# machnguon.net
KiCad netlist of a schematic drawn in Altium Designer
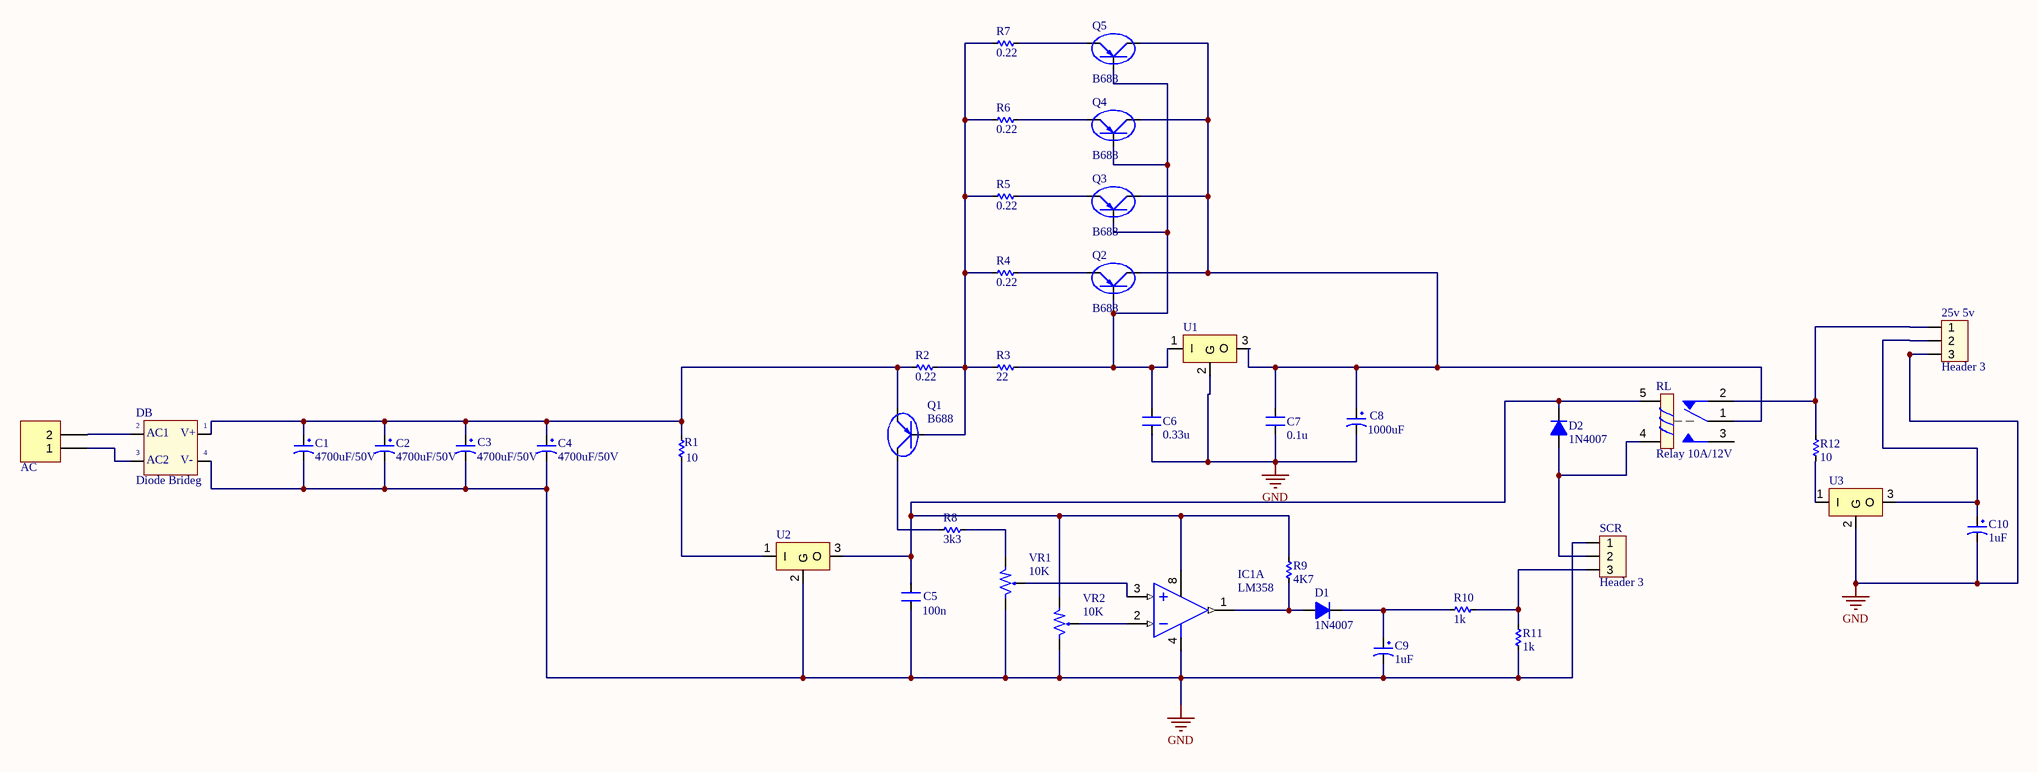
[diagram p0: machnguon.SchDoc]

(export (version "E")
  (design (tool "Eeschema 10.0.6"))
  (components
    (comp (ref "25v 5v")
      (value "Header 3")
      (footprint "HED3")
      (description "Header 3 (Green)")
      (libsource (lib "syhaunguyen__1") (part "Hed3"))
    )
    (comp (ref "AC")
      (value "Header 2_1")
      (footprint "HED2")
      (description "Header, 2-Pin")
      (fields (field (name "MANUFACTURER") "Generic Components"))
      (libsource (lib "syhaunguyen__1") (part "Header 2_1"))
    )
    (comp (ref "C1")
      (value "4700uF/50V")
      (footprint "CP4/8.5")
      (description "Cap 4700uF/50V")
      (libsource (lib "syhaunguyen__1") (part "CP7"))
    )
    (comp (ref "C2")
      (value "4700uF/50V")
      (footprint "CP4/8.5")
      (description "Cap 4700uF/50V")
      (libsource (lib "syhaunguyen__1") (part "CP7"))
    )
    (comp (ref "C3")
      (value "4700uF/50V")
      (footprint "CP4/8.5")
      (description "Cap 4700uF/50V")
      (libsource (lib "syhaunguyen__1") (part "CP7"))
    )
    (comp (ref "C4")
      (value "4700uF/50V")
      (footprint "CP4/8.5")
      (description "Cap 4700uF/50V")
      (libsource (lib "syhaunguyen__1") (part "CP7"))
    )
    (comp (ref "C5")
      (value "100n")
      (footprint "CN1")
      (description "Cap np  1pF - 472pF")
      (libsource (lib "syhaunguyen__1") (part "CN1"))
    )
    (comp (ref "C6")
      (value "0.33u")
      (footprint "CN1")
      (description "Cap np  1pF - 472pF")
      (libsource (lib "syhaunguyen__1") (part "CN1"))
    )
    (comp (ref "C7")
      (value "0.1u")
      (footprint "CN1")
      (description "Cap np  1pF - 472pF")
      (libsource (lib "syhaunguyen__1") (part "CN1"))
    )
    (comp (ref "C8")
      (value "1000uF")
      (footprint "CP1.5/3.4")
      (description "Cap 1000uF/16V - 220uF/50V")
      (libsource (lib "syhaunguyen__1") (part "CP4"))
    )
    (comp (ref "C9")
      (value "1uF")
      (footprint "CP1/2")
      (description "Cap P  0,1uF < 22uF , 16 - 50V")
      (libsource (lib "syhaunguyen__1") (part "CP1"))
    )
    (comp (ref "C10")
      (value "1uF")
      (footprint "CP1/2")
      (description "Cap P  0,1uF < 22uF , 16 - 50V")
      (libsource (lib "syhaunguyen__1") (part "CP1"))
    )
    (comp (ref "D1")
      (value "1N4007")
      (footprint "D1A")
      (description "Diode 1A")
      (libsource (lib "syhaunguyen__1") (part "D1A"))
    )
    (comp (ref "D2")
      (value "1N4007")
      (footprint "D1A")
      (description "Diode 1A")
      (libsource (lib "syhaunguyen__1") (part "D1A"))
    )
    (comp (ref "DB")
      (value "Diode Brideg")
      (footprint "CAU 5A")
      (description "Convert AC to DC voltage, 4 pin")
      (libsource (lib "syhaunguyen__1") (part "DB"))
    )
    (comp (ref "IC1")
      (value "LM358")
      (footprint "DIP8")
      (description "Low-Power Dual Operational Amplifier")
      (libsource (lib "Library1") (part "LM358"))
    )
    (comp (ref "Q1")
      (value "B688")
      (footprint "QTO-247")
      (description "Transistor Power Supply")
      (libsource (lib "") (part "B688_1"))
    )
    (comp (ref "Q2")
      (value "B688")
      (footprint "QTO-247")
      (description "Transistor Power Supply")
      (libsource (lib "syhaunguyen__1") (part "B688"))
    )
    (comp (ref "Q3")
      (value "B688")
      (footprint "QTO-247")
      (description "Transistor Power Supply")
      (libsource (lib "syhaunguyen__1") (part "B688"))
    )
    (comp (ref "Q4")
      (value "B688")
      (footprint "QTO-247")
      (description "Transistor Power Supply")
      (libsource (lib "syhaunguyen__1") (part "B688"))
    )
    (comp (ref "Q5")
      (value "B688")
      (footprint "QTO-247")
      (description "Transistor Power Supply")
      (libsource (lib "syhaunguyen__1") (part "B688"))
    )
    (comp (ref "R1")
      (value "10")
      (footprint "RES-2W")
      (description "Res")
      (fields
        (field (name "MANUFACTURER") "Generic Components")
        (field (name "PUBLISHER") "Altium Hobart Technology Centre")
      )
      (libsource (lib "Library1") (part "Res"))
    )
    (comp (ref "R2")
      (value "0.22")
      (footprint "RES-2W")
      (description "Res")
      (fields
        (field (name "MANUFACTURER") "Generic Components")
        (field (name "PUBLISHER") "Altium Hobart Technology Centre")
      )
      (libsource (lib "Library1") (part "Res"))
    )
    (comp (ref "R3")
      (value "22")
      (footprint "RES-2W")
      (description "Res")
      (fields
        (field (name "MANUFACTURER") "Generic Components")
        (field (name "PUBLISHER") "Altium Hobart Technology Centre")
      )
      (libsource (lib "Library1") (part "Res"))
    )
    (comp (ref "R4")
      (value "0.22")
      (footprint "RES-2W")
      (description "Res")
      (fields
        (field (name "MANUFACTURER") "Generic Components")
        (field (name "PUBLISHER") "Altium Hobart Technology Centre")
      )
      (libsource (lib "Library1") (part "Res"))
    )
    (comp (ref "R5")
      (value "0.22")
      (footprint "RES-2W")
      (description "Res")
      (fields
        (field (name "MANUFACTURER") "Generic Components")
        (field (name "PUBLISHER") "Altium Hobart Technology Centre")
      )
      (libsource (lib "Library1") (part "Res"))
    )
    (comp (ref "R6")
      (value "0.22")
      (footprint "RES-2W")
      (description "Res")
      (fields
        (field (name "MANUFACTURER") "Generic Components")
        (field (name "PUBLISHER") "Altium Hobart Technology Centre")
      )
      (libsource (lib "Library1") (part "Res"))
    )
    (comp (ref "R7")
      (value "0.22")
      (footprint "RES-2W")
      (description "Res")
      (fields
        (field (name "MANUFACTURER") "Generic Components")
        (field (name "PUBLISHER") "Altium Hobart Technology Centre")
      )
      (libsource (lib "Library1") (part "Res"))
    )
    (comp (ref "R8")
      (value "3k3")
      (footprint "RES-2W")
      (description "Res")
      (fields
        (field (name "MANUFACTURER") "Generic Components")
        (field (name "PUBLISHER") "Altium Hobart Technology Centre")
      )
      (libsource (lib "Library1") (part "Res"))
    )
    (comp (ref "R9")
      (value "4K7")
      (footprint "RES-2W")
      (description "Res")
      (fields
        (field (name "MANUFACTURER") "Generic Components")
        (field (name "PUBLISHER") "Altium Hobart Technology Centre")
      )
      (libsource (lib "Library1") (part "Res"))
    )
    (comp (ref "R10")
      (value "1k")
      (footprint "RES-2W")
      (description "Res")
      (fields
        (field (name "MANUFACTURER") "Generic Components")
        (field (name "PUBLISHER") "Altium Hobart Technology Centre")
      )
      (libsource (lib "Library1") (part "Res"))
    )
    (comp (ref "R11")
      (value "1k")
      (footprint "RES-2W")
      (description "Res")
      (fields
        (field (name "MANUFACTURER") "Generic Components")
        (field (name "PUBLISHER") "Altium Hobart Technology Centre")
      )
      (libsource (lib "Library1") (part "Res"))
    )
    (comp (ref "R12")
      (value "10")
      (footprint "RES-2W")
      (description "Res")
      (fields
        (field (name "MANUFACTURER") "Generic Components")
        (field (name "PUBLISHER") "Altium Hobart Technology Centre")
      )
      (libsource (lib "Library1") (part "Res"))
    )
    (comp (ref "RL")
      (value "Relay 10A/12V")
      (footprint "RELAY 5")
      (description "Relay SPDT,10A - 12VDC 5 Pin")
      (libsource (lib "Library1") (part "Relay 5"))
    )
    (comp (ref "SCR")
      (value "Header 3")
      (footprint "HED3")
      (description "Header 3 (Green)")
      (libsource (lib "syhaunguyen__1") (part "Hed3"))
    )
    (comp (ref "U1")
      (value "LM78xx")
      (footprint "TO220-123")
      (description "Positive Voltage Regulator")
      (fields (field (name "PUBLISHER") "Altium Limited"))
      (libsource (lib "Library1") (part "LM78xx"))
    )
    (comp (ref "U2")
      (value "LM78xx")
      (footprint "TO220-123")
      (description "Positive Voltage Regulator")
      (fields (field (name "PUBLISHER") "Altium Limited"))
      (libsource (lib "Library1") (part "LM78xx"))
    )
    (comp (ref "U3")
      (value "LM78xx")
      (footprint "TO220-123")
      (description "Positive Voltage Regulator")
      (fields (field (name "PUBLISHER") "Altium Limited"))
      (libsource (lib "Library1") (part "LM78xx"))
    )
    (comp (ref "VR1")
      (value "10K")
      (footprint "VR1")
      (description "Var Resistor")
      (libsource (lib "syhaunguyen__1") (part "VR1"))
    )
    (comp (ref "VR2")
      (value "10K")
      (footprint "VR1")
      (description "Var Resistor")
      (libsource (lib "syhaunguyen__1") (part "VR1"))
    )
  )
  (nets
    (net (code "1") (name "GND") (class "Default")
      (node (ref "25v 5v") (pin "3") (pinfunction "3_3") (pintype "passive"))
      (node (ref "C1") (pin "2") (pinfunction "2_2") (pintype "passive"))
      (node (ref "C10") (pin "2") (pinfunction "2_2") (pintype "passive"))
      (node (ref "C2") (pin "2") (pinfunction "2_2") (pintype "passive"))
      (node (ref "C3") (pin "2") (pinfunction "2_2") (pintype "passive"))
      (node (ref "C4") (pin "2") (pinfunction "2_2") (pintype "passive"))
      (node (ref "C5") (pin "1") (pinfunction "1_1") (pintype "passive"))
      (node (ref "C6") (pin "1") (pinfunction "1_1") (pintype "passive"))
      (node (ref "C7") (pin "1") (pinfunction "1_1") (pintype "passive"))
      (node (ref "C8") (pin "2") (pinfunction "2_2") (pintype "passive"))
      (node (ref "C9") (pin "2") (pinfunction "2_2") (pintype "passive"))
      (node (ref "DB") (pin "4") (pinfunction "-V_OUT_4") (pintype "passive"))
      (node (ref "IC1") (pin "4") (pinfunction "-V_4") (pintype "passive"))
      (node (ref "R11") (pin "2") (pinfunction "2_2") (pintype "passive"))
      (node (ref "SCR") (pin "1") (pinfunction "1_1") (pintype "passive"))
      (node (ref "U1") (pin "2") (pinfunction "G_2") (pintype "power_in"))
      (node (ref "U2") (pin "2") (pinfunction "G_2") (pintype "power_in"))
      (node (ref "U3") (pin "2") (pinfunction "G_2") (pintype "power_in"))
      (node (ref "VR1") (pin "3") (pinfunction "3_3") (pintype "passive"))
      (node (ref "VR2") (pin "3") (pinfunction "3_3") (pintype "passive"))
    )
    (net (code "2") (name "Net-(25v 5v-Pad1)") (class "Default")
      (node (ref "25v 5v") (pin "1") (pinfunction "1_1") (pintype "passive"))
      (node (ref "R12") (pin "1") (pinfunction "1_1") (pintype "passive"))
      (node (ref "RL") (pin "2") (pinfunction "2_2") (pintype "passive"))
    )
    (net (code "3") (name "Net-(D1-A)") (class "Default")
      (node (ref "D1") (pin "1") (pinfunction "A_1") (pintype "passive"))
      (node (ref "IC1") (pin "1") (pinfunction "OUT_1") (pintype "output"))
      (node (ref "R9") (pin "2") (pinfunction "2_2") (pintype "passive"))
    )
    (net (code "4") (name "Net-(D1-K)") (class "Default")
      (node (ref "C9") (pin "1") (pinfunction "1_1") (pintype "passive"))
      (node (ref "D1") (pin "2") (pinfunction "K_2") (pintype "passive"))
      (node (ref "R10") (pin "2") (pinfunction "2_2") (pintype "passive"))
    )
    (net (code "5") (name "Net-(D2-A)") (class "Default")
      (node (ref "D2") (pin "1") (pinfunction "A_1") (pintype "passive"))
      (node (ref "RL") (pin "4") (pinfunction "4_4") (pintype "passive"))
      (node (ref "SCR") (pin "2") (pinfunction "2_2") (pintype "passive"))
    )
    (net (code "6") (name "Net-(D2-K)") (class "Default")
      (node (ref "C5") (pin "2") (pinfunction "2_2") (pintype "passive"))
      (node (ref "D2") (pin "2") (pinfunction "K_2") (pintype "passive"))
      (node (ref "IC1") (pin "8") (pinfunction "+V_8") (pintype "passive"))
      (node (ref "R9") (pin "1") (pinfunction "1_1") (pintype "passive"))
      (node (ref "RL") (pin "5") (pinfunction "5_5") (pintype "passive"))
      (node (ref "U2") (pin "3") (pinfunction "O_3") (pintype "power_in"))
      (node (ref "VR2") (pin "1") (pinfunction "1_1") (pintype "passive"))
    )
    (net (code "7") (name "Net-(DB-+V_OUT)") (class "Default")
      (node (ref "C1") (pin "1") (pinfunction "1_1") (pintype "passive"))
      (node (ref "C2") (pin "1") (pinfunction "1_1") (pintype "passive"))
      (node (ref "C3") (pin "1") (pinfunction "1_1") (pintype "passive"))
      (node (ref "C4") (pin "1") (pinfunction "1_1") (pintype "passive"))
      (node (ref "DB") (pin "1") (pinfunction "+V_OUT_1") (pintype "passive"))
      (node (ref "Q1") (pin "3") (pinfunction "E_3") (pintype "passive"))
      (node (ref "R1") (pin "1") (pinfunction "1_1") (pintype "passive"))
      (node (ref "R2") (pin "2") (pinfunction "2_2") (pintype "passive"))
    )
    (net (code "8") (name "Net-(DB-AC1)") (class "Default")
      (node (ref "AC") (pin "2") (pinfunction "2_2") (pintype "passive"))
      (node (ref "DB") (pin "2") (pinfunction "AC1_2") (pintype "passive"))
    )
    (net (code "9") (name "Net-(DB-AC2)") (class "Default")
      (node (ref "AC") (pin "1") (pinfunction "1_1") (pintype "passive"))
      (node (ref "DB") (pin "3") (pinfunction "AC2_3") (pintype "passive"))
    )
    (net (code "10") (name "Net-(IC1A-IN+)") (class "Default")
      (node (ref "IC1") (pin "3") (pinfunction "IN+_3") (pintype "input"))
      (node (ref "VR1") (pin "2") (pinfunction "2_2") (pintype "passive"))
    )
    (net (code "11") (name "Net-(IC1A-IN-)") (class "Default")
      (node (ref "IC1") (pin "2") (pinfunction "IN-_2") (pintype "input"))
      (node (ref "VR2") (pin "2") (pinfunction "2_2") (pintype "passive"))
    )
    (net (code "12") (name "Net-(Q1-B)") (class "Default")
      (node (ref "Q1") (pin "1") (pinfunction "B_1") (pintype "passive"))
      (node (ref "R2") (pin "1") (pinfunction "1_1") (pintype "passive"))
      (node (ref "R3") (pin "2") (pinfunction "2_2") (pintype "passive"))
      (node (ref "R4") (pin "2") (pinfunction "2_2") (pintype "passive"))
      (node (ref "R5") (pin "2") (pinfunction "2_2") (pintype "passive"))
      (node (ref "R6") (pin "2") (pinfunction "2_2") (pintype "passive"))
      (node (ref "R7") (pin "2") (pinfunction "2_2") (pintype "passive"))
    )
    (net (code "13") (name "Net-(Q1-C)") (class "Default")
      (node (ref "Q1") (pin "2") (pinfunction "C_2") (pintype "passive"))
      (node (ref "R8") (pin "2") (pinfunction "2_2") (pintype "passive"))
    )
    (net (code "14") (name "Net-(Q2-B)") (class "Default")
      (node (ref "C6") (pin "2") (pinfunction "2_2") (pintype "passive"))
      (node (ref "Q2") (pin "1") (pinfunction "B_1") (pintype "passive"))
      (node (ref "Q3") (pin "1") (pinfunction "B_1") (pintype "passive"))
      (node (ref "Q4") (pin "1") (pinfunction "B_1") (pintype "passive"))
      (node (ref "Q5") (pin "1") (pinfunction "B_1") (pintype "passive"))
      (node (ref "R3") (pin "1") (pinfunction "1_1") (pintype "passive"))
      (node (ref "U1") (pin "1") (pinfunction "I_1") (pintype "power_in"))
    )
    (net (code "15") (name "Net-(Q2-C)") (class "Default")
      (node (ref "C7") (pin "2") (pinfunction "2_2") (pintype "passive"))
      (node (ref "C8") (pin "1") (pinfunction "1_1") (pintype "passive"))
      (node (ref "Q2") (pin "2") (pinfunction "C_2") (pintype "passive"))
      (node (ref "Q3") (pin "2") (pinfunction "C_2") (pintype "passive"))
      (node (ref "Q4") (pin "2") (pinfunction "C_2") (pintype "passive"))
      (node (ref "Q5") (pin "2") (pinfunction "C_2") (pintype "passive"))
      (node (ref "RL") (pin "1") (pinfunction "1_1") (pintype "passive"))
      (node (ref "U1") (pin "3") (pinfunction "O_3") (pintype "power_in"))
    )
    (net (code "16") (name "Net-(Q2-E)") (class "Default")
      (node (ref "Q2") (pin "3") (pinfunction "E_3") (pintype "passive"))
      (node (ref "R4") (pin "1") (pinfunction "1_1") (pintype "passive"))
    )
    (net (code "17") (name "Net-(Q3-E)") (class "Default")
      (node (ref "Q3") (pin "3") (pinfunction "E_3") (pintype "passive"))
      (node (ref "R5") (pin "1") (pinfunction "1_1") (pintype "passive"))
    )
    (net (code "18") (name "Net-(Q4-E)") (class "Default")
      (node (ref "Q4") (pin "3") (pinfunction "E_3") (pintype "passive"))
      (node (ref "R6") (pin "1") (pinfunction "1_1") (pintype "passive"))
    )
    (net (code "19") (name "Net-(Q5-E)") (class "Default")
      (node (ref "Q5") (pin "3") (pinfunction "E_3") (pintype "passive"))
      (node (ref "R7") (pin "1") (pinfunction "1_1") (pintype "passive"))
    )
    (net (code "20") (name "Net-(R8-Pad1)") (class "Default")
      (node (ref "R8") (pin "1") (pinfunction "1_1") (pintype "passive"))
      (node (ref "VR1") (pin "1") (pinfunction "1_1") (pintype "passive"))
    )
    (net (code "21") (name "Net-(R10-Pad1)") (class "Default")
      (node (ref "R10") (pin "1") (pinfunction "1_1") (pintype "passive"))
      (node (ref "R11") (pin "1") (pinfunction "1_1") (pintype "passive"))
      (node (ref "SCR") (pin "3") (pinfunction "3_3") (pintype "passive"))
    )
    (net (code "22") (name "Net-(U2-I)") (class "Default")
      (node (ref "R1") (pin "2") (pinfunction "2_2") (pintype "passive"))
      (node (ref "U2") (pin "1") (pinfunction "I_1") (pintype "power_in"))
    )
    (net (code "23") (name "Net-(U3-I)") (class "Default")
      (node (ref "R12") (pin "2") (pinfunction "2_2") (pintype "passive"))
      (node (ref "U3") (pin "1") (pinfunction "I_1") (pintype "power_in"))
    )
    (net (code "24") (name "Net-(U3-O)") (class "Default")
      (node (ref "25v 5v") (pin "2") (pinfunction "2_2") (pintype "passive"))
      (node (ref "C10") (pin "1") (pinfunction "1_1") (pintype "passive"))
      (node (ref "U3") (pin "3") (pinfunction "O_3") (pintype "power_in"))
    )
    (net (code "25") (name "unconnected-(RL-Pad3)") (class "Default")
      (node (ref "RL") (pin "3") (pinfunction "3_3") (pintype "passive"))
    )
  )
)
